# daglig.net
KiCad netlist of a schematic drawn in EAGLE
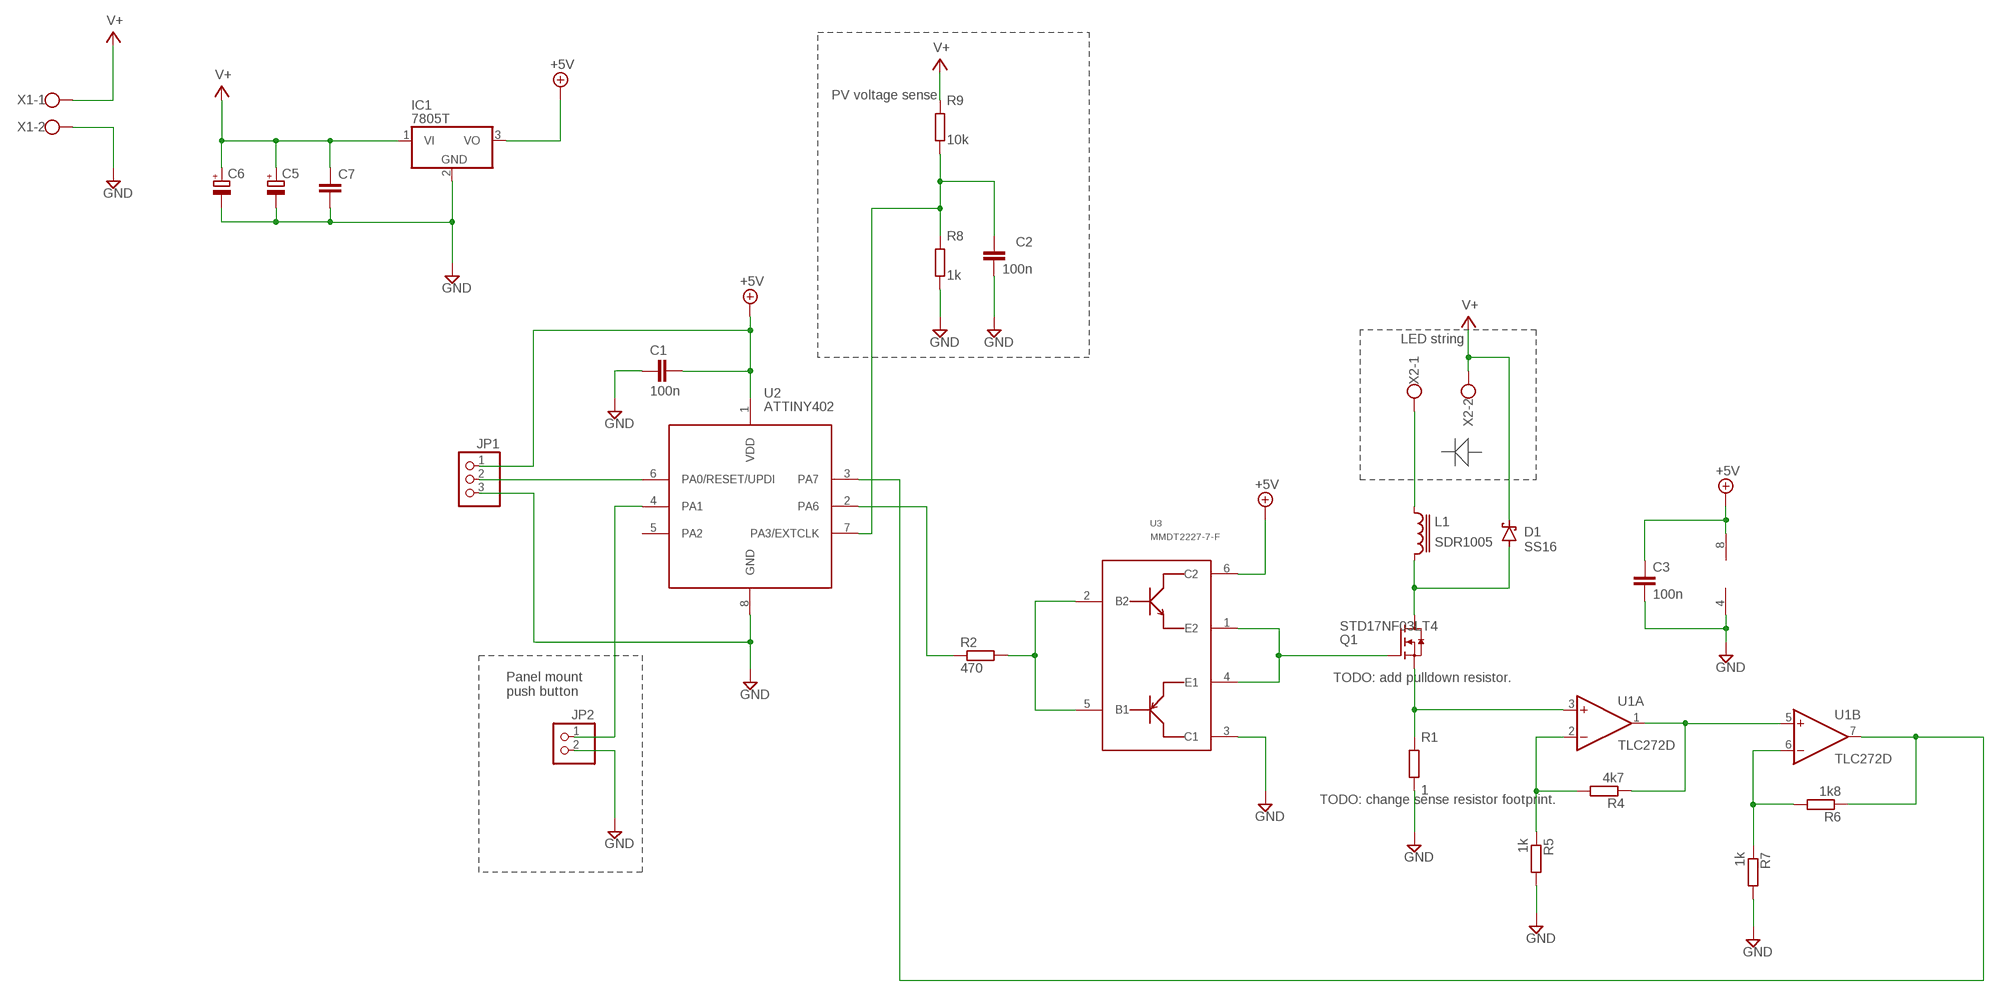
[diagram p0: schematic, sheet 1]

(export (version "E")
  (design (tool "Eeschema 10.0.6"))
  (components
    (comp (ref "C1")
      (value "100n")
      (footprint "eagle-import:C0805")
      (libsource (lib "eagle-import") (part "C-EUC0805"))
    )
    (comp (ref "C2")
      (value "100n")
      (footprint "eagle-import:C0805")
      (libsource (lib "eagle-import") (part "C-EUC0805"))
    )
    (comp (ref "C3")
      (value "100n")
      (footprint "eagle-import:C0805")
      (libsource (lib "eagle-import") (part "C-EUC0805"))
    )
    (comp (ref "C5")
      (value "CPOL-EUE5-10.5")
      (footprint "eagle-import:E5-10,5")
      (libsource (lib "eagle-import") (part "CPOL-EUE5-10.5"))
    )
    (comp (ref "C6")
      (value "CPOL-EUE5-10.5")
      (footprint "eagle-import:E5-10,5")
      (libsource (lib "eagle-import") (part "CPOL-EUE5-10.5"))
    )
    (comp (ref "C7")
      (value "C-EUC0805")
      (footprint "eagle-import:C0805")
      (libsource (lib "eagle-import") (part "C-EUC0805"))
    )
    (comp (ref "D1")
      (value "SS16")
      (footprint "eagle-import:DO214AC")
      (libsource (lib "eagle-import") (part "SS16"))
    )
    (comp (ref "IC1")
      (value "7805T")
      (footprint "eagle-import:TO220H")
      (libsource (lib "eagle-import") (part "78T05"))
    )
    (comp (ref "JP1")
      (value "PINHD-1X3")
      (footprint "eagle-import:1X03")
      (libsource (lib "eagle-import") (part "PINHD-1X3"))
    )
    (comp (ref "JP2")
      (value "PINHD-1X2")
      (footprint "eagle-import:1X02")
      (libsource (lib "eagle-import") (part "PINHD-1X2"))
    )
    (comp (ref "L1")
      (value "SDR1005")
      (footprint "eagle-import:SDR1005")
      (libsource (lib "eagle-import") (part "SDR1005"))
    )
    (comp (ref "Q1")
      (value "STD17NF03LT4")
      (footprint "eagle-import:TO252")
      (libsource (lib "eagle-import") (part "STD17NF03LT4"))
    )
    (comp (ref "R1")
      (value "1")
      (footprint "eagle-import:R2512")
      (libsource (lib "eagle-import") (part "R-EU_R2512"))
    )
    (comp (ref "R2")
      (value "470")
      (footprint "eagle-import:R0805")
      (libsource (lib "eagle-import") (part "R-EU_R0805"))
    )
    (comp (ref "R4")
      (value "4k7")
      (footprint "eagle-import:R0805")
      (libsource (lib "eagle-import") (part "R-EU_R0805"))
    )
    (comp (ref "R5")
      (value "1k")
      (footprint "eagle-import:R0805")
      (libsource (lib "eagle-import") (part "R-EU_R0805"))
    )
    (comp (ref "R6")
      (value "1k8")
      (footprint "eagle-import:R0805")
      (libsource (lib "eagle-import") (part "R-EU_R0805"))
    )
    (comp (ref "R7")
      (value "1k")
      (footprint "eagle-import:R0805")
      (libsource (lib "eagle-import") (part "R-EU_R0805"))
    )
    (comp (ref "R8")
      (value "1k")
      (footprint "eagle-import:R0805")
      (libsource (lib "eagle-import") (part "R-EU_R0805"))
    )
    (comp (ref "R9")
      (value "10k")
      (footprint "eagle-import:R0805")
      (libsource (lib "eagle-import") (part "R-EU_R0805"))
    )
    (comp (ref "U1")
      (value "TLC272D")
      (footprint "eagle-import:SO08")
      (libsource (lib "eagle-import") (part "TLC272D"))
    )
    (comp (ref "U2")
      (value "ATTINY402")
      (footprint "eagle-import:SO8")
      (libsource (lib "eagle-import") (part "ATTINY402"))
    )
    (comp (ref "U3")
      (value "MMDT2227-7-F")
      (footprint "eagle-import:SOT363_PHILIPS")
      (libsource (lib "eagle-import") (part "MMDT2227-7-F"))
    )
    (comp (ref "X1")
      (value "W237-102")
      (footprint "eagle-import:W237-102")
      (fields (field (name "MPN") "237-102"))
      (libsource (lib "eagle-import") (part "W237-102"))
    )
    (comp (ref "X2")
      (value "W237-102")
      (footprint "eagle-import:W237-102")
      (fields (field (name "MPN") "237-102"))
      (libsource (lib "eagle-import") (part "W237-102"))
    )
  )
  (nets
    (net (code "1") (name "+5V") (class "Default")
      (node (ref "C1") (pin "2") (pinfunction "2_2") (pintype "passive"))
      (node (ref "C3") (pin "1") (pinfunction "1_1") (pintype "passive"))
      (node (ref "IC1") (pin "3") (pinfunction "VO_3") (pintype "passive"))
      (node (ref "JP1") (pin "1") (pinfunction "1_1") (pintype "passive"))
      (node (ref "U1") (pin "8") (pinfunction "V+_8") (pintype "power_in"))
      (node (ref "U2") (pin "1") (pinfunction "VDD_1") (pintype "power_in"))
      (node (ref "U3") (pin "6") (pinfunction "C2_6") (pintype "passive"))
    )
    (net (code "2") (name "GND") (class "Default")
      (node (ref "C1") (pin "1") (pinfunction "1_1") (pintype "passive"))
      (node (ref "C2") (pin "2") (pinfunction "2_2") (pintype "passive"))
      (node (ref "C3") (pin "2") (pinfunction "2_2") (pintype "passive"))
      (node (ref "C5") (pin "-") (pinfunction "-_-") (pintype "passive"))
      (node (ref "C6") (pin "-") (pinfunction "-_-") (pintype "passive"))
      (node (ref "C7") (pin "2") (pinfunction "2_2") (pintype "passive"))
      (node (ref "IC1") (pin "2") (pinfunction "GND_2") (pintype "passive"))
      (node (ref "JP1") (pin "3") (pinfunction "3_3") (pintype "passive"))
      (node (ref "JP2") (pin "2") (pinfunction "2_2") (pintype "passive"))
      (node (ref "R1") (pin "1") (pinfunction "1_1") (pintype "passive"))
      (node (ref "R5") (pin "2") (pinfunction "2_2") (pintype "passive"))
      (node (ref "R7") (pin "2") (pinfunction "2_2") (pintype "passive"))
      (node (ref "R8") (pin "1") (pinfunction "1_1") (pintype "passive"))
      (node (ref "U1") (pin "4") (pinfunction "V-_4") (pintype "power_in"))
      (node (ref "U2") (pin "8") (pinfunction "GND_8") (pintype "power_in"))
      (node (ref "U3") (pin "3") (pinfunction "C1_3") (pintype "passive"))
      (node (ref "X1") (pin "2") (pinfunction "KL_2") (pintype "passive"))
    )
    (net (code "3") (name "Net-(Q1-D)") (class "Default")
      (node (ref "D1") (pin "A") (pinfunction "A_A") (pintype "passive"))
      (node (ref "L1") (pin "2") (pinfunction "2_2") (pintype "passive"))
      (node (ref "Q1") (pin "3") (pinfunction "D_3") (pintype "passive"))
    )
    (net (code "4") (name "Net-(Q1-G)") (class "Default")
      (node (ref "Q1") (pin "1") (pinfunction "G_1") (pintype "passive"))
      (node (ref "U3") (pin "1") (pinfunction "E2_1") (pintype "passive"))
      (node (ref "U3") (pin "4") (pinfunction "E1_4") (pintype "passive"))
    )
    (net (code "5") (name "Net-(Q1-S)") (class "Default")
      (node (ref "Q1") (pin "2") (pinfunction "S_2") (pintype "passive"))
      (node (ref "R1") (pin "2") (pinfunction "2_2") (pintype "passive"))
      (node (ref "U1") (pin "3") (pinfunction "+IN_3") (pintype "input"))
    )
    (net (code "6") (name "Net-(U1A--IN)") (class "Default")
      (node (ref "R4") (pin "2") (pinfunction "2_2") (pintype "passive"))
      (node (ref "R5") (pin "1") (pinfunction "1_1") (pintype "passive"))
      (node (ref "U1") (pin "2") (pinfunction "-IN_2") (pintype "input"))
    )
    (net (code "7") (name "Net-(U1A-OUT)") (class "Default")
      (node (ref "R4") (pin "1") (pinfunction "1_1") (pintype "passive"))
      (node (ref "U1") (pin "1") (pinfunction "OUT_1") (pintype "output"))
      (node (ref "U1") (pin "5") (pinfunction "+IN_5") (pintype "input"))
    )
    (net (code "8") (name "Net-(U1B--IN)") (class "Default")
      (node (ref "R6") (pin "2") (pinfunction "2_2") (pintype "passive"))
      (node (ref "R7") (pin "1") (pinfunction "1_1") (pintype "passive"))
      (node (ref "U1") (pin "6") (pinfunction "-IN_6") (pintype "input"))
    )
    (net (code "9") (name "Net-(U1B-OUT)") (class "Default")
      (node (ref "R6") (pin "1") (pinfunction "1_1") (pintype "passive"))
      (node (ref "U1") (pin "7") (pinfunction "OUT_7") (pintype "output"))
      (node (ref "U2") (pin "3") (pinfunction "PA7_3") (pintype "bidirectional"))
    )
    (net (code "10") (name "Net-(U2-PA0{slash}RESET{slash}UPDI)") (class "Default")
      (node (ref "JP1") (pin "2") (pinfunction "2_2") (pintype "passive"))
      (node (ref "U2") (pin "6") (pinfunction "PA0/RESET/UPDI_6") (pintype "bidirectional"))
    )
    (net (code "11") (name "Net-(U2-PA1)") (class "Default")
      (node (ref "JP2") (pin "1") (pinfunction "1_1") (pintype "passive"))
      (node (ref "U2") (pin "4") (pinfunction "PA1_4") (pintype "bidirectional"))
    )
    (net (code "12") (name "Net-(U2-PA3{slash}EXTCLK)") (class "Default")
      (node (ref "C2") (pin "1") (pinfunction "1_1") (pintype "passive"))
      (node (ref "R8") (pin "2") (pinfunction "2_2") (pintype "passive"))
      (node (ref "R9") (pin "1") (pinfunction "1_1") (pintype "passive"))
      (node (ref "U2") (pin "7") (pinfunction "PA3/EXTCLK_7") (pintype "bidirectional"))
    )
    (net (code "13") (name "Net-(U2-PA6)") (class "Default")
      (node (ref "R2") (pin "1") (pinfunction "1_1") (pintype "passive"))
      (node (ref "U2") (pin "2") (pinfunction "PA6_2") (pintype "bidirectional"))
    )
    (net (code "14") (name "Net-(U3-B1)") (class "Default")
      (node (ref "R2") (pin "2") (pinfunction "2_2") (pintype "passive"))
      (node (ref "U3") (pin "2") (pinfunction "B2_2") (pintype "passive"))
      (node (ref "U3") (pin "5") (pinfunction "B1_5") (pintype "passive"))
    )
    (net (code "15") (name "Net-(X2A-KL)") (class "Default")
      (node (ref "L1") (pin "1") (pinfunction "1_1") (pintype "passive"))
      (node (ref "X2") (pin "1") (pinfunction "KL_1") (pintype "passive"))
    )
    (net (code "16") (name "V+") (class "Default")
      (node (ref "C5") (pin "+") (pinfunction "+_+") (pintype "passive"))
      (node (ref "C6") (pin "+") (pinfunction "+_+") (pintype "passive"))
      (node (ref "C7") (pin "1") (pinfunction "1_1") (pintype "passive"))
      (node (ref "D1") (pin "C") (pinfunction "C_C") (pintype "passive"))
      (node (ref "IC1") (pin "1") (pinfunction "VI_1") (pintype "input"))
      (node (ref "R9") (pin "2") (pinfunction "2_2") (pintype "passive"))
      (node (ref "X1") (pin "1") (pinfunction "KL_1") (pintype "passive"))
      (node (ref "X2") (pin "2") (pinfunction "KL_2") (pintype "passive"))
    )
    (net (code "17") (name "unconnected-(U2-PA2-Pad5)") (class "Default")
      (node (ref "U2") (pin "5") (pinfunction "PA2_5") (pintype "bidirectional"))
    )
  )
)
